# USB_Connectors.net
KiCad netlist of a schematic drawn in Altium Designer
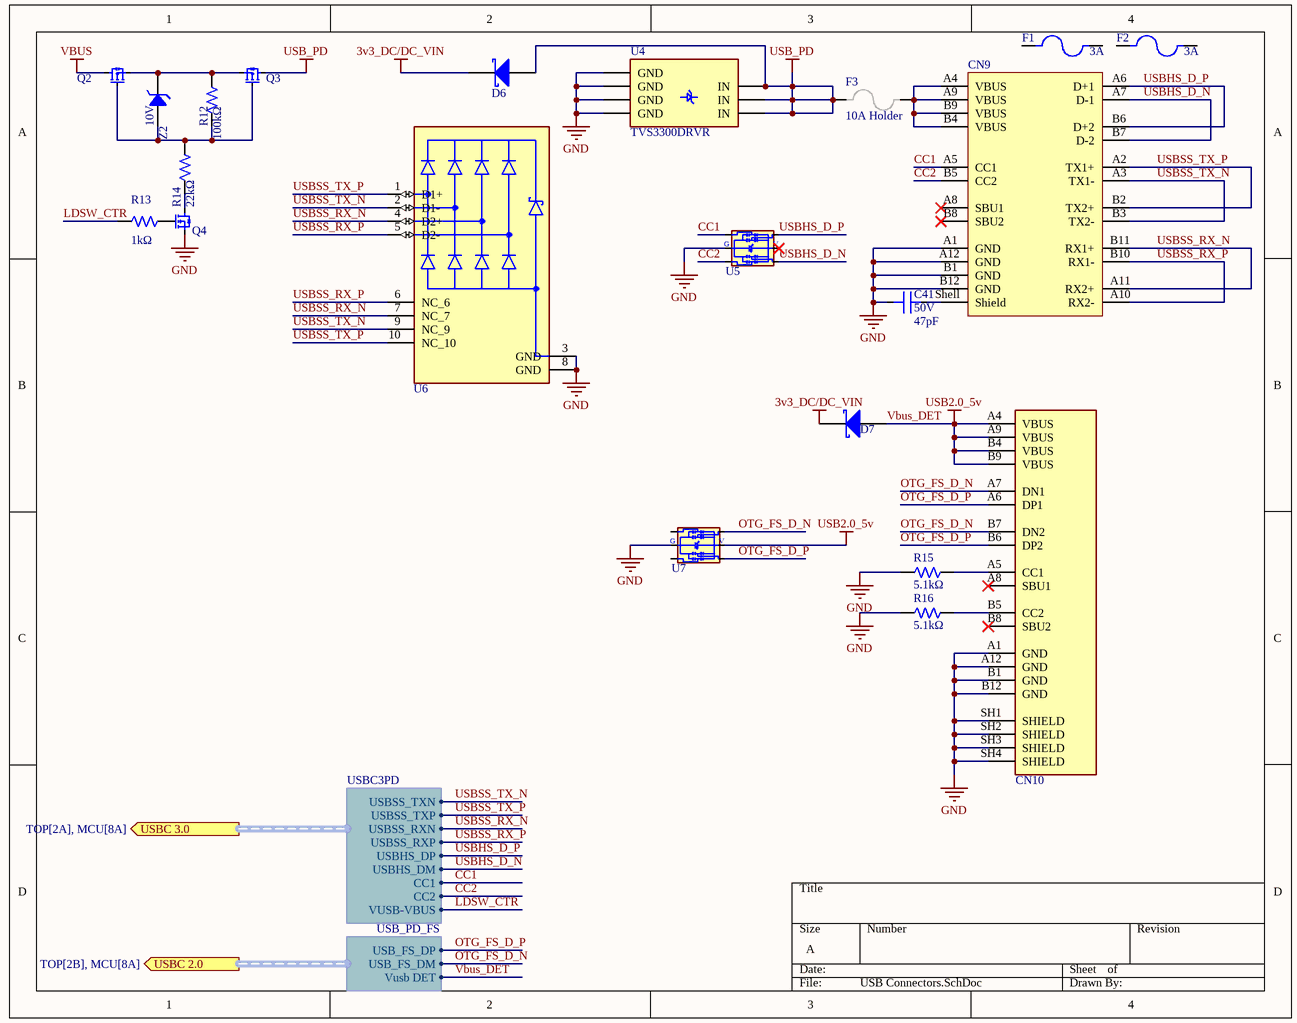
[diagram p0: USB Connectors.SchDoc]

(export (version "E")
  (design (tool "Eeschema 10.0.6"))
  (components
    (comp (ref "C41")
      (value "CAP CER 47pF 50V C0G 0603")
      (footprint "C_0603")
      (description "47pF ±5% 50V Ceramic Capacitor C0G 0603")
      (fields
        (field (name "VOLTAGE RATING") "50V")
        (field (name "CAPACITANCE") "47pF")
        (field (name "LCSC PART #") "C1671")
        (field (name "MANUFACTURER") "Samsung Electro-Mechanics")
      )
      (libsource (lib "Database_Libs_MICH_1") (part "CAP"))
    )
    (comp (ref "CN9")
      (value "CONN RCPT USB 3.1 Type-C 24POS SMD R/A")
      (footprint "CONN_TYPE-C_24P_SMD_RA")
      (description "USB-C (USB TYPE-C) Receptacle Connector 24 Position Surface Mount, Right Angle")
      (fields (field (name "MPN") "TYPE-C 24P QT 143") (field (name "LCSC PART #") "C5156605"))
      (libsource (lib "Database_Libs_MICH_1") (part "CONN_USB_C_24P"))
    )
    (comp (ref "CN10")
      (value "CONN RCPT USB 3.1 Type-C 16POS TH R/A")
      (footprint "CONN_TYPE-C_16P_TH_RA")
      (description "USB-C (USB TYPE-C) Receptacle Connector 16 Position Right Angle")
      (fields (field (name "MPN") "TYPEC-306DDW-ARP16") (field (name "LCSC PART #") "C2840393"))
      (libsource (lib "Database_Libs_MICH_1") (part "CONN_USB_C_16P"))
    )
    (comp (ref "D6")
      (value "DIODE SCHOTTKY 40V SOD-323")
      (footprint "SOD323")
      (description "Diode 40V 1A Surface Mount SOD-323")
      (fields (field (name "MPN") "1N5819WS") (field (name "LCSC PART #") "C191023"))
      (libsource (lib "Database_Libs_MICH_1") (part "DIODE_SCHOTTKY"))
    )
    (comp (ref "D7")
      (value "DIODE SCHOTTKY 40V SOD-323")
      (footprint "SOD323")
      (description "Diode 40V 1A Surface Mount SOD-323")
      (fields (field (name "MPN") "1N5819WS") (field (name "LCSC PART #") "C191023"))
      (libsource (lib "Database_Libs_MICH_1") (part "DIODE_SCHOTTKY"))
    )
    (comp (ref "F1")
      (value "3A")
      (description "FUSE BRD MNT 3A 2410")
      (libsource (lib "MI_Personal_special") (part "JFC2410-1300FS"))
    )
    (comp (ref "F2")
      (value "3A")
      (description "FUSE BRD MNT 3A 2410")
      (libsource (lib "MI_Personal_special") (part "JFC2410-1300FS"))
    )
    (comp (ref "F3")
      (value "10A Holder")
      (footprint "FUSE_SMD 2410 HOLDER")
      (description "FUSE BLOK CARTRIDGE 125V 10A SMD")
      (libsource (lib "MI_Personal_special") (part "01550900M"))
    )
    (comp (ref "Q2")
      (value "MOSFET P-CH 30V 4A SOT-23")
      (footprint "SOT23")
      (description "30V 4A Surface Mount SOT-23")
      (fields (field (name "MPN") "AO3401A") (field (name "LCSC PART #") "C15127"))
      (libsource (lib "Database_Libs_MICH_1") (part "MOSFET_P_SOT-23"))
    )
    (comp (ref "Q3")
      (value "MOSFET P-CH 30V 4A SOT-23")
      (footprint "SOT23")
      (description "30V 4A Surface Mount SOT-23")
      (fields (field (name "MPN") "AO3401A") (field (name "LCSC PART #") "C15127"))
      (libsource (lib "Database_Libs_MICH_1") (part "MOSFET_P_SOT-23"))
    )
    (comp (ref "Q4")
      (value "MOSFET N-CH 30V SOT-23-3L")
      (footprint "SOT23")
      (description "N-Channel 30V Surface Mount SOT-23-3L")
      (fields (field (name "MPN") "AO3400A") (field (name "LCSC PART #") "C20917"))
      (libsource (lib "Database_Libs_MICH_1") (part "MOSFET_N_SOT-23"))
    )
    (comp (ref "R12")
      (value "RES 100kΩ ±1% 100mW 0603")
      (footprint "R_0603")
      (description "100kΩ ±1% 100mW 0603 Thick Film Resistor")
      (fields
        (field (name "RESISTANCE") "100kΩ")
        (field (name "LCSC PART #") "C25803")
        (field (name "MPN") "0603WAF1003T5E")
      )
      (libsource (lib "Database_Libs_MICH_1") (part "RES"))
    )
    (comp (ref "R13")
      (value "RES 1kΩ ±1% 100mW 0603")
      (footprint "R_0603")
      (description "1kΩ ±1% 100mW 0603 Thick Film Resistor")
      (fields
        (field (name "RESISTANCE") "1kΩ")
        (field (name "MPN") "0603WAF1001T5E")
        (field (name "POWER") "100mW")
      )
      (libsource (lib "Database_Libs_MICH_1") (part "RES"))
    )
    (comp (ref "R14")
      (value "RES 22kΩ ±1% 100mW 0603")
      (footprint "R_0603")
      (description "22kΩ ±1% 100mW 0603 Thick Film Resistor")
      (fields
        (field (name "RESISTANCE") "22kΩ")
        (field (name "LCSC PART #") "C31850")
        (field (name "MPN") "0603WAF2202T5E")
      )
      (libsource (lib "Database_Libs_MICH_1") (part "RES"))
    )
    (comp (ref "R15")
      (value "RES 5.1kΩ ±1% 100mW 0603")
      (footprint "R_0603")
      (description "5.1kΩ ±1% 100mW 0603 Thick Film Resistor")
      (fields
        (field (name "RESISTANCE") "5.1kΩ")
        (field (name "MPN") "0603WAF5101T5E")
        (field (name "POWER") "100mW")
      )
      (libsource (lib "Database_Libs_MICH_1") (part "RES"))
    )
    (comp (ref "R16")
      (value "RES 5.1kΩ ±1% 100mW 0603")
      (footprint "R_0603")
      (description "5.1kΩ ±1% 100mW 0603 Thick Film Resistor")
      (fields
        (field (name "RESISTANCE") "5.1kΩ")
        (field (name "MPN") "0603WAF5101T5E")
        (field (name "POWER") "100mW")
      )
      (libsource (lib "Database_Libs_MICH_1") (part "RES"))
    )
    (comp (ref "U4")
      (value "TVS3300DRVR")
      (footprint "WSON-6(2x2)")
      (description "Surge Protection IC Surface Mount WSON-6(2x2)")
      (fields (field (name "LCSC PART #") "C2863624") (field (name "MANUFACTURER") "TI"))
      (libsource (lib "Database_Libs_MICH_1") (part "TVS3300DRVR"))
    )
    (comp (ref "U5")
      (value "ESD DIODE 5.5VWM 18VC SOT-23-6")
      (footprint "SOT-23-6")
      (description "18VC Clamp 4A@8/20us Ipp ESD DIODE SOT-23-6")
      (fields (field (name "MPN") "AOZ8904CIL") (field (name "LCSC PART #") "C2649893"))
      (libsource (lib "Database_Libs_MICH_1") (part "DIODE_TVS_4CH_SOT-23-6"))
    )
    (comp (ref "U6")
      (value "TVS DIODE 5.5VWM 14VC USON-10(1x2.5)")
      (footprint "USON-10")
      (description "14VC Clamp 2.5A@8/20us Ipp TVS DIODE USON-10(1x2.5)")
      (fields (field (name "MPN") "TPD4E05U06DQAR") (field (name "LCSC PART #") "C138714"))
      (libsource (lib "Database_Libs_MICH_1") (part "DIODE_TVS_4CH_USON-10"))
    )
    (comp (ref "U7")
      (value "ESD DIODE 5.5VWM 18VC SOT-23-6")
      (footprint "SOT-23-6")
      (description "18VC Clamp 4A@8/20us Ipp ESD DIODE SOT-23-6")
      (fields (field (name "MPN") "AOZ8904CIL") (field (name "LCSC PART #") "C2649893"))
      (libsource (lib "Database_Libs_MICH_1") (part "DIODE_TVS_4CH_SOT-23-6"))
    )
    (comp (ref "Z2")
      (value "DIODE ZENER 10V 500mW SOD-123")
      (footprint "SOD123")
      (description "Zener Diode Independent 10V 500mW Surface Mount SOD-123")
      (fields
        (field (name "MPN") "MM1Z10B")
        (field (name "LCSC PART #") "C22466341")
        (field (name "ZENER VOLTAGE") "10V")
      )
      (libsource (lib "Database_Libs_MICH_1") (part "DIODE_ZENER"))
    )
  )
  (nets
    (net (code "3") (name "/CC1") (class "Default")
      (node (ref "CN9") (pin "A5") (pinfunction "CC1_A5") (pintype "passive"))
      (node (ref "U5") (pin "1") (pinfunction "1_1") (pintype "passive"))
    )
    (net (code "4") (name "/CC2") (class "Default")
      (node (ref "CN9") (pin "B5") (pinfunction "CC2_B5") (pintype "passive"))
      (node (ref "U5") (pin "3") (pinfunction "3_3") (pintype "passive"))
    )
    (net (code "5") (name "/LDSW_CTR") (class "Default")
      (node (ref "R13") (pin "1") (pinfunction "1_1") (pintype "passive"))
    )
    (net (code "6") (name "/OTG_FS_D_N") (class "Default")
      (node (ref "CN10") (pin "A7") (pinfunction "DN1_A7") (pintype "passive"))
      (node (ref "CN10") (pin "B7") (pinfunction "DN2_B7") (pintype "passive"))
      (node (ref "U7") (pin "6") (pinfunction "6_6") (pintype "passive"))
    )
    (net (code "7") (name "/OTG_FS_D_P") (class "Default")
      (node (ref "CN10") (pin "A6") (pinfunction "DP1_A6") (pintype "passive"))
      (node (ref "CN10") (pin "B6") (pinfunction "DP2_B6") (pintype "passive"))
      (node (ref "U7") (pin "4") (pinfunction "4_4") (pintype "passive"))
    )
    (net (code "8") (name "/USBHS_D_N") (class "Default")
      (node (ref "CN9") (pin "A7") (pinfunction "D-1_A7") (pintype "passive"))
      (node (ref "CN9") (pin "B7") (pinfunction "D-2_B7") (pintype "passive"))
      (node (ref "U5") (pin "4") (pinfunction "4_4") (pintype "passive"))
    )
    (net (code "9") (name "/USBHS_D_P") (class "Default")
      (node (ref "CN9") (pin "A6") (pinfunction "D+1_A6") (pintype "passive"))
      (node (ref "CN9") (pin "B6") (pinfunction "D+2_B6") (pintype "passive"))
      (node (ref "U5") (pin "6") (pinfunction "6_6") (pintype "passive"))
    )
    (net (code "10") (name "/USBSS_RX_N") (class "Default")
      (node (ref "CN9") (pin "A11") (pinfunction "RX2+_A11") (pintype "passive"))
      (node (ref "CN9") (pin "B11") (pinfunction "RX1+_B11") (pintype "passive"))
      (node (ref "U6") (pin "4") (pinfunction "D2+_4") (pintype "bidirectional"))
      (node (ref "U6") (pin "7") (pinfunction "NC_7_7") (pintype "passive"))
    )
    (net (code "11") (name "/USBSS_RX_P") (class "Default")
      (node (ref "CN9") (pin "A10") (pinfunction "RX2-_A10") (pintype "passive"))
      (node (ref "CN9") (pin "B10") (pinfunction "RX1-_B10") (pintype "passive"))
      (node (ref "U6") (pin "5") (pinfunction "D2-_5") (pintype "bidirectional"))
      (node (ref "U6") (pin "6") (pinfunction "NC_6_6") (pintype "passive"))
    )
    (net (code "12") (name "/USBSS_TX_N") (class "Default")
      (node (ref "CN9") (pin "A3") (pinfunction "TX1-_A3") (pintype "passive"))
      (node (ref "CN9") (pin "B3") (pinfunction "TX2-_B3") (pintype "passive"))
      (node (ref "U6") (pin "2") (pinfunction "D1-_2") (pintype "bidirectional"))
      (node (ref "U6") (pin "9") (pinfunction "NC_9_9") (pintype "passive"))
    )
    (net (code "13") (name "/USBSS_TX_P") (class "Default")
      (node (ref "CN9") (pin "A2") (pinfunction "TX1+_A2") (pintype "passive"))
      (node (ref "CN9") (pin "B2") (pinfunction "TX2+_B2") (pintype "passive"))
      (node (ref "U6") (pin "1") (pinfunction "D1+_1") (pintype "bidirectional"))
      (node (ref "U6") (pin "10") (pinfunction "NC_10_10") (pintype "passive"))
    )
    (net (code "16") (name "3v3_DC{slash}DC_VIN") (class "Default")
      (node (ref "D6") (pin "2") (pinfunction "K_2") (pintype "passive"))
      (node (ref "D7") (pin "2") (pinfunction "K_2") (pintype "passive"))
    )
    (net (code "17") (name "GND") (class "Default")
      (node (ref "C41") (pin "1") (pinfunction "1_1") (pintype "passive"))
      (node (ref "CN10") (pin "A1") (pinfunction "GND_A1") (pintype "passive"))
      (node (ref "CN10") (pin "A12") (pinfunction "GND_A12") (pintype "passive"))
      (node (ref "CN10") (pin "B1") (pinfunction "GND_B1") (pintype "passive"))
      (node (ref "CN10") (pin "B12") (pinfunction "GND_B12") (pintype "passive"))
      (node (ref "CN10") (pin "SH1") (pinfunction "SHIELD_SH1") (pintype "passive"))
      (node (ref "CN10") (pin "SH2") (pinfunction "SHIELD_SH2") (pintype "passive"))
      (node (ref "CN10") (pin "SH3") (pinfunction "SHIELD_SH3") (pintype "passive"))
      (node (ref "CN10") (pin "SH4") (pinfunction "SHIELD_SH4") (pintype "passive"))
      (node (ref "CN9") (pin "A1") (pinfunction "GND_A1") (pintype "passive"))
      (node (ref "CN9") (pin "A12") (pinfunction "GND_A12") (pintype "passive"))
      (node (ref "CN9") (pin "B1") (pinfunction "GND_B1") (pintype "passive"))
      (node (ref "CN9") (pin "B12") (pinfunction "GND_B12") (pintype "passive"))
      (node (ref "Q4") (pin "2") (pinfunction "SOURCE_2") (pintype "passive"))
      (node (ref "R15") (pin "1") (pinfunction "1_1") (pintype "passive"))
      (node (ref "R16") (pin "1") (pinfunction "1_1") (pintype "passive"))
      (node (ref "U4") (pin "1") (pinfunction "GND_1") (pintype "power_in"))
      (node (ref "U4") (pin "2") (pinfunction "GND_2") (pintype "power_in"))
      (node (ref "U4") (pin "3") (pinfunction "GND_3") (pintype "power_in"))
      (node (ref "U4") (pin "7") (pinfunction "GND_7") (pintype "power_in"))
      (node (ref "U5") (pin "2") (pinfunction "2_2") (pintype "passive"))
      (node (ref "U6") (pin "3") (pinfunction "GND_3") (pintype "power_in"))
      (node (ref "U6") (pin "8") (pinfunction "GND_8") (pintype "power_in"))
      (node (ref "U7") (pin "2") (pinfunction "2_2") (pintype "passive"))
    )
    (net (code "18") (name "Net-(CN9-Shield)") (class "Default")
      (node (ref "C41") (pin "2") (pinfunction "2_2") (pintype "passive"))
      (node (ref "CN9") (pin "Shell") (pinfunction "Shield_Shell") (pintype "passive"))
    )
    (net (code "19") (name "Net-(CN9-VBUS-PadA4)") (class "Default")
      (node (ref "CN9") (pin "A4") (pinfunction "VBUS_A4") (pintype "passive"))
      (node (ref "CN9") (pin "A9") (pinfunction "VBUS_A9") (pintype "passive"))
      (node (ref "CN9") (pin "B4") (pinfunction "VBUS_B4") (pintype "passive"))
      (node (ref "CN9") (pin "B9") (pinfunction "VBUS_B9") (pintype "passive"))
      (node (ref "F3") (pin "2") (pinfunction "2_2") (pintype "passive"))
    )
    (net (code "20") (name "Net-(CN10-CC1)") (class "Default")
      (node (ref "CN10") (pin "A5") (pinfunction "CC1_A5") (pintype "passive"))
      (node (ref "R15") (pin "2") (pinfunction "2_2") (pintype "passive"))
    )
    (net (code "21") (name "Net-(CN10-CC2)") (class "Default")
      (node (ref "CN10") (pin "B5") (pinfunction "CC2_B5") (pintype "passive"))
      (node (ref "R16") (pin "2") (pinfunction "2_2") (pintype "passive"))
    )
    (net (code "22") (name "Net-(Q2-GATE)") (class "Default")
      (node (ref "Q2") (pin "1") (pinfunction "GATE_1") (pintype "passive"))
      (node (ref "Q3") (pin "1") (pinfunction "GATE_1") (pintype "passive"))
      (node (ref "R12") (pin "1") (pinfunction "1_1") (pintype "passive"))
      (node (ref "R14") (pin "2") (pinfunction "2_2") (pintype "passive"))
      (node (ref "Z2") (pin "1") (pinfunction "1_1") (pintype "passive"))
    )
    (net (code "23") (name "Net-(Q2-SOURCE)") (class "Default")
      (node (ref "Q2") (pin "2") (pinfunction "SOURCE_2") (pintype "passive"))
      (node (ref "Q3") (pin "2") (pinfunction "SOURCE_2") (pintype "passive"))
      (node (ref "R12") (pin "2") (pinfunction "2_2") (pintype "passive"))
      (node (ref "Z2") (pin "2") (pinfunction "2_2") (pintype "passive"))
    )
    (net (code "24") (name "Net-(Q4-DRAIN)") (class "Default")
      (node (ref "Q4") (pin "3") (pinfunction "DRAIN_3") (pintype "passive"))
      (node (ref "R14") (pin "1") (pinfunction "1_1") (pintype "passive"))
    )
    (net (code "25") (name "Net-(Q4-GATE)") (class "Default")
      (node (ref "Q4") (pin "1") (pinfunction "GATE_1") (pintype "passive"))
      (node (ref "R13") (pin "2") (pinfunction "2_2") (pintype "passive"))
    )
    (net (code "26") (name "USB2.0_5v") (class "Default")
      (node (ref "CN10") (pin "A4") (pinfunction "VBUS_A4") (pintype "passive"))
      (node (ref "CN10") (pin "A9") (pinfunction "VBUS_A9") (pintype "passive"))
      (node (ref "CN10") (pin "B4") (pinfunction "VBUS_B4") (pintype "passive"))
      (node (ref "CN10") (pin "B9") (pinfunction "VBUS_B9") (pintype "passive"))
      (node (ref "D7") (pin "1") (pinfunction "A_1") (pintype "passive"))
      (node (ref "U7") (pin "5") (pinfunction "5_5") (pintype "passive"))
    )
    (net (code "27") (name "USB_PD") (class "Default")
      (node (ref "D6") (pin "1") (pinfunction "A_1") (pintype "passive"))
      (node (ref "F3") (pin "1") (pinfunction "1_1") (pintype "passive"))
      (node (ref "Q3") (pin "3") (pinfunction "DRAIN_3") (pintype "passive"))
      (node (ref "U4") (pin "4") (pinfunction "IN_4") (pintype "power_in"))
      (node (ref "U4") (pin "5") (pinfunction "IN_5") (pintype "power_in"))
      (node (ref "U4") (pin "6") (pinfunction "IN_6") (pintype "power_in"))
    )
    (net (code "28") (name "VBUS") (class "Default")
      (node (ref "Q2") (pin "3") (pinfunction "DRAIN_3") (pintype "passive"))
    )
    (net (code "29") (name "unconnected-(CN9-SBU1-PadA8)") (class "Default")
      (node (ref "CN9") (pin "A8") (pinfunction "SBU1_A8") (pintype "passive+no_connect"))
    )
    (net (code "30") (name "unconnected-(CN9-SBU2-PadB8)") (class "Default")
      (node (ref "CN9") (pin "B8") (pinfunction "SBU2_B8") (pintype "passive+no_connect"))
    )
    (net (code "31") (name "unconnected-(CN10-SBU1-PadA8)") (class "Default")
      (node (ref "CN10") (pin "A8") (pinfunction "SBU1_A8") (pintype "passive+no_connect"))
    )
    (net (code "32") (name "unconnected-(CN10-SBU2-PadB8)") (class "Default")
      (node (ref "CN10") (pin "B8") (pinfunction "SBU2_B8") (pintype "passive+no_connect"))
    )
    (net (code "33") (name "unconnected-(F1-Pad1)") (class "Default")
      (node (ref "F1") (pin "1") (pinfunction "1_1") (pintype "passive"))
    )
    (net (code "34") (name "unconnected-(F1-Pad2)") (class "Default")
      (node (ref "F1") (pin "2") (pinfunction "2_2") (pintype "passive"))
    )
    (net (code "35") (name "unconnected-(F2-Pad1)") (class "Default")
      (node (ref "F2") (pin "1") (pinfunction "1_1") (pintype "passive"))
    )
    (net (code "36") (name "unconnected-(F2-Pad2)") (class "Default")
      (node (ref "F2") (pin "2") (pinfunction "2_2") (pintype "passive"))
    )
    (net (code "37") (name "unconnected-(U5-Pad5)") (class "Default")
      (node (ref "U5") (pin "5") (pinfunction "5_5") (pintype "passive+no_connect"))
    )
    (net (code "38") (name "unconnected-(U7-Pad1)") (class "Default")
      (node (ref "U7") (pin "1") (pinfunction "1_1") (pintype "passive"))
    )
    (net (code "39") (name "unconnected-(U7-Pad3)") (class "Default")
      (node (ref "U7") (pin "3") (pinfunction "3_3") (pintype "passive"))
    )
  )
)
